# 1-Schematic_Task.net
KiCad netlist of a schematic drawn in EasyEDA
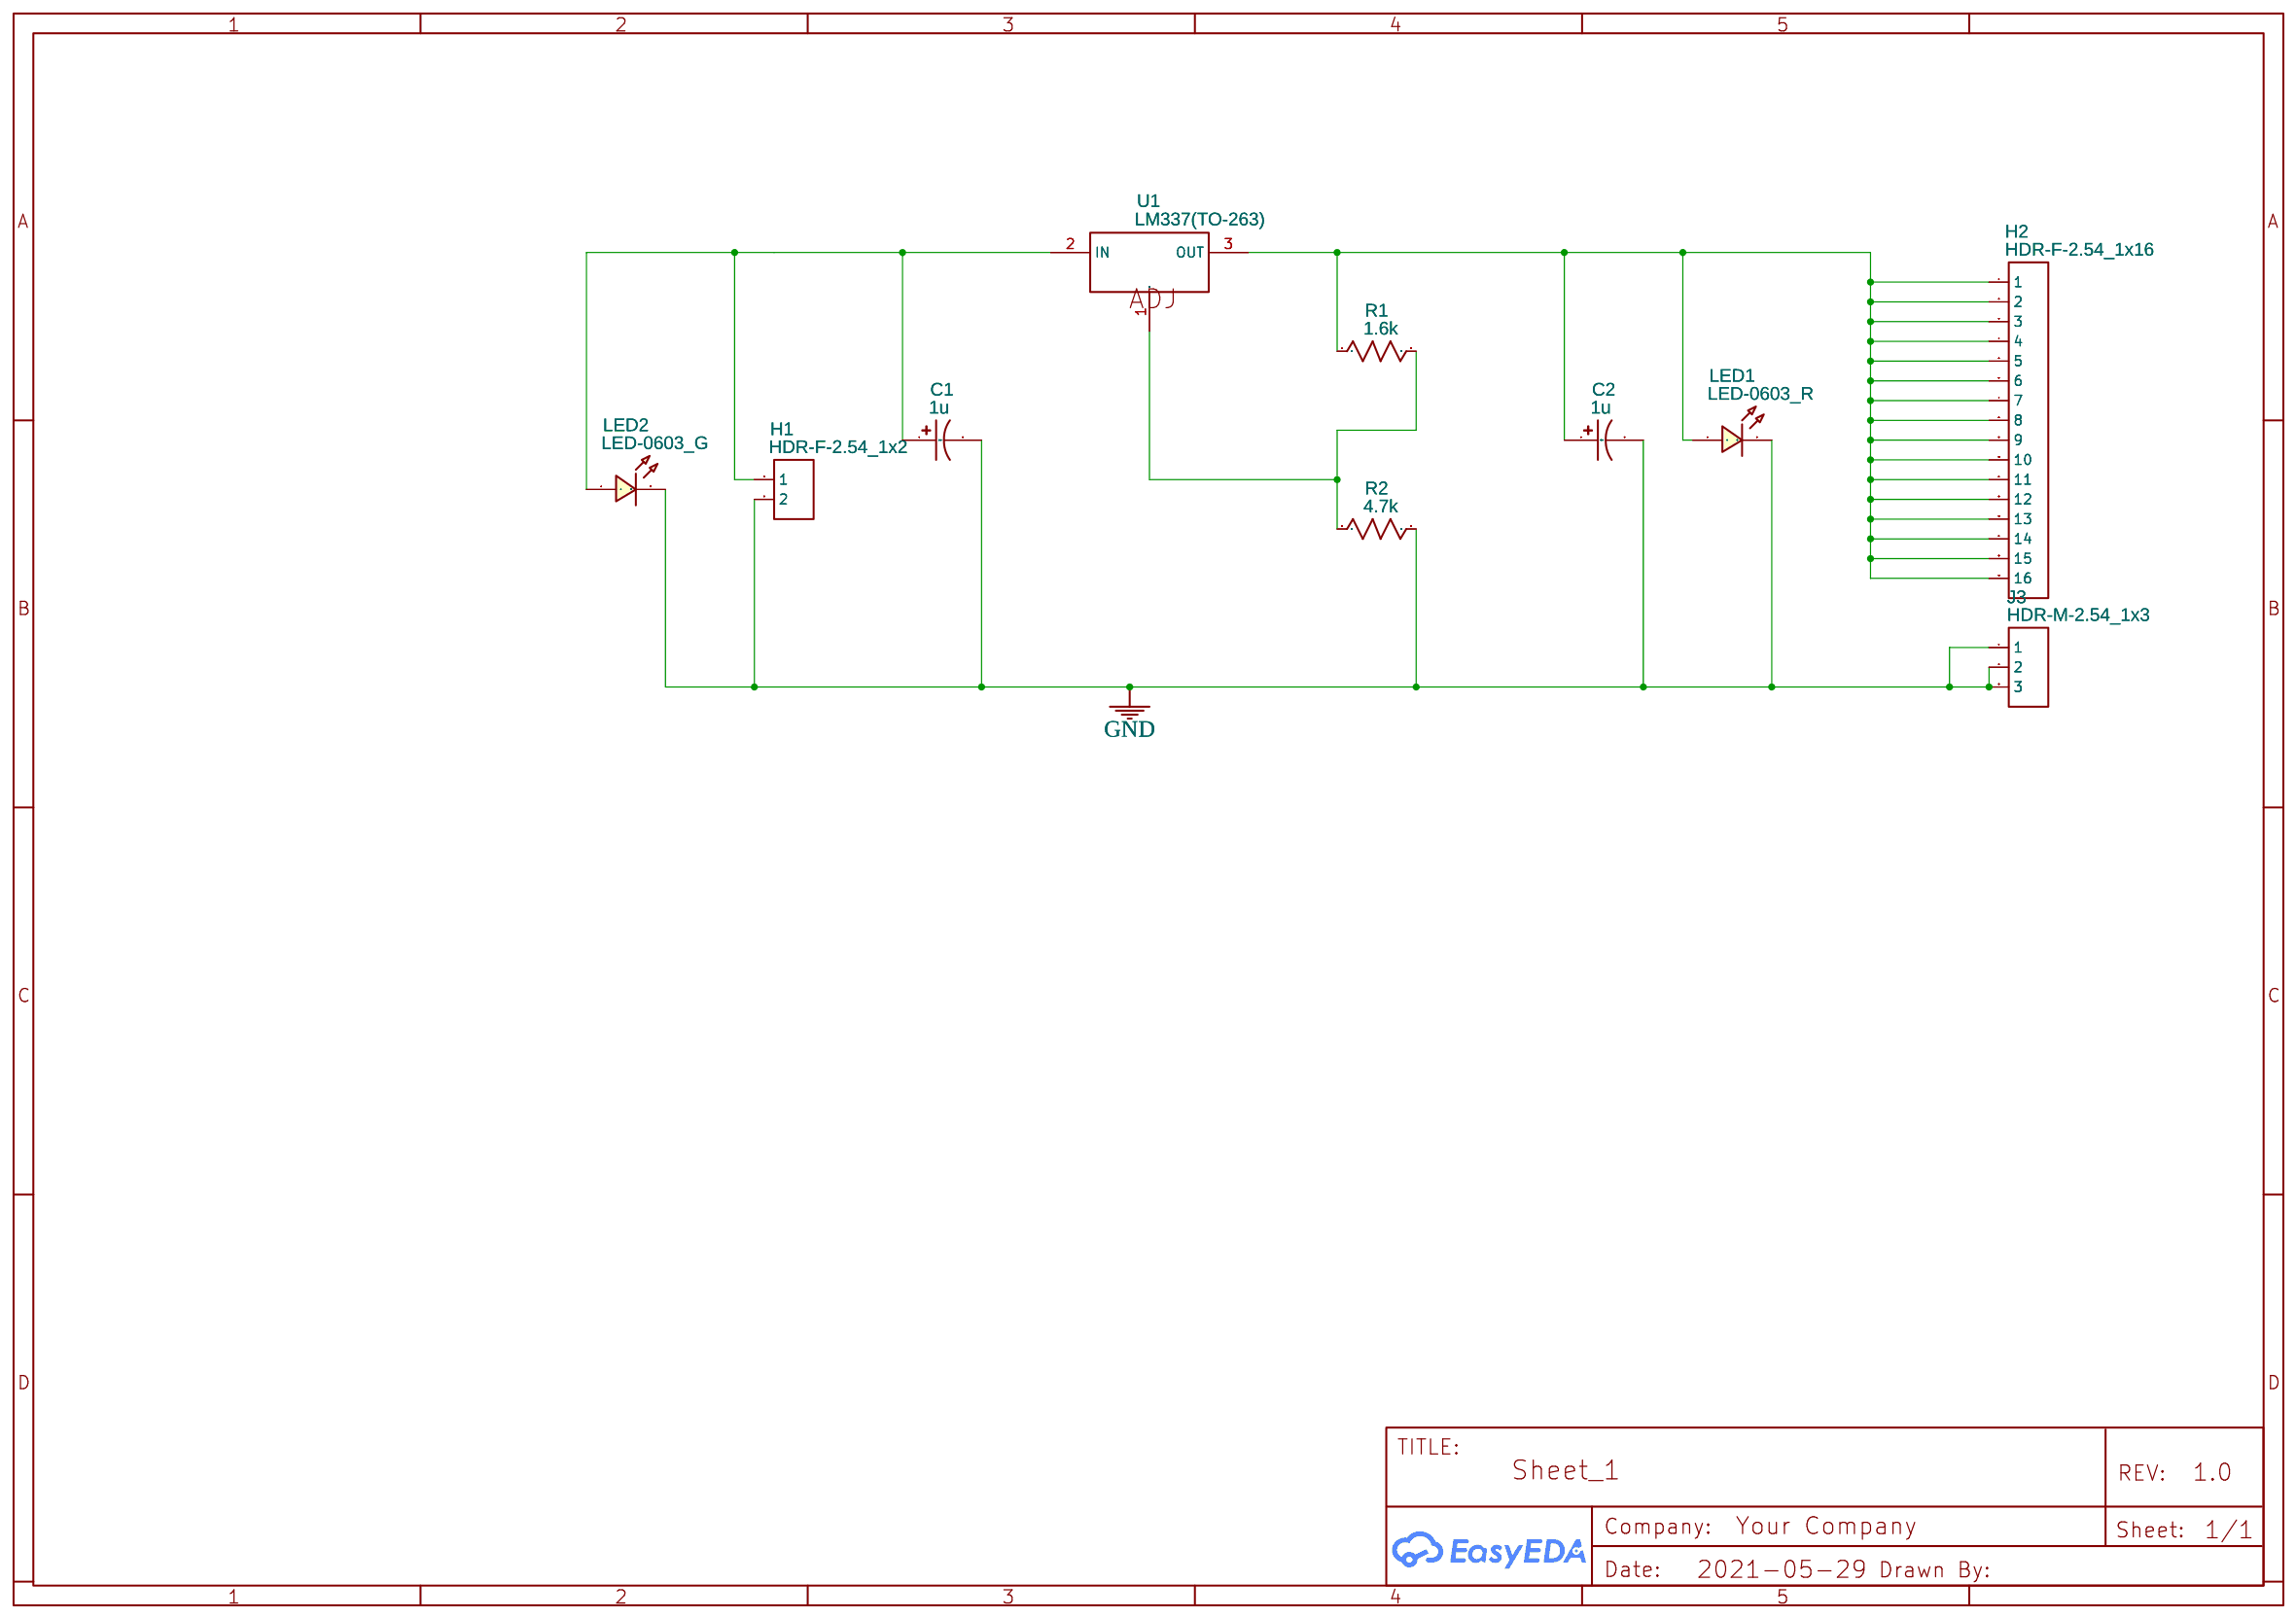
[diagram p0: schematic sheet]

(export (version "E")
  (design (tool "Eeschema 10.0.6"))
  (components
    (comp (ref "C1") (value "1u") (libsource (lib "") (part "C_Tan_SMD_A_US")))
    (comp (ref "C2") (value "1u") (libsource (lib "") (part "C_Tan_SMD_A_US")))
    (comp (ref "H1")
      (value "HDR-F-2.54_1x2")
      (fields (field (name "BOM_Supplier Part") "C49661"))
      (libsource (lib "") (part "HDR-F-2.54_1x2"))
    )
    (comp (ref "H2")
      (value "HDR-F-2.54_1x16")
      (fields (field (name "BOM_Supplier Part") "C66987"))
      (libsource (lib "") (part "HDR-F-2.54_1x16"))
    )
    (comp (ref "J3")
      (value "HDR-M-2.54_1x3")
      (fields (field (name "BOM_Supplier Part") "C180248"))
      (libsource (lib "") (part "HDR-M-2.54_1x3"))
    )
    (comp (ref "LED1")
      (value "LED-0603_R")
      (fields
        (field (name "BOM_Manufacturer Part") "19-217/R6C-AL1M2VY/3T")
        (field (name "BOM_Supplier Part") "C72044")
      )
      (libsource (lib "") (part "LED-0603_R"))
    )
    (comp (ref "LED2")
      (value "LED-0603_G")
      (fields
        (field (name "BOM_Manufacturer Part") "19-217/GHC-YR1S2/3T")
        (field (name "BOM_Supplier Part") "C72043")
      )
      (libsource (lib "") (part "LED-0603_G"))
    )
    (comp (ref "R1") (value "1.6k") (libsource (lib "") (part "R_0603_US")))
    (comp (ref "R2") (value "4.7k") (libsource (lib "") (part "R_0603_US")))
    (comp (ref "U1")
      (value "LM337(TO-263)")
      (fields (field (name "BOM_Manufacturer Part") "LM337D2TG") (field (name "BOM_Supplier Part") "C146782"))
      (libsource (lib "") (part "LM337(TO-263)"))
    )
  )
  (nets
    (net (code "1") (name "GND") (class "Default")
      (node (ref "C1") (pin "2") (pinfunction "2_2") (pintype "unspecified"))
      (node (ref "C2") (pin "2") (pinfunction "2_2") (pintype "unspecified"))
      (node (ref "H1") (pin "2") (pinfunction "2_2") (pintype "input"))
      (node (ref "J3") (pin "1") (pinfunction "1_1") (pintype "input"))
      (node (ref "J3") (pin "2") (pinfunction "2_2") (pintype "input"))
      (node (ref "J3") (pin "3") (pinfunction "3_3") (pintype "input"))
      (node (ref "LED1") (pin "2") (pinfunction "2_2") (pintype "unspecified"))
      (node (ref "LED2") (pin "2") (pinfunction "2_2") (pintype "unspecified"))
      (node (ref "R2") (pin "2") (pinfunction "2_2") (pintype "unspecified"))
    )
    (net (code "2") (name "Net-(U1-ADJ)") (class "Default")
      (node (ref "R1") (pin "2") (pinfunction "2_2") (pintype "unspecified"))
      (node (ref "R2") (pin "1") (pinfunction "1_1") (pintype "unspecified"))
      (node (ref "U1") (pin "1") (pinfunction "ADJ_1") (pintype "passive"))
    )
    (net (code "3") (name "Net-(U1-IN)") (class "Default")
      (node (ref "C1") (pin "1") (pinfunction "1_1") (pintype "unspecified"))
      (node (ref "H1") (pin "1") (pinfunction "1_1") (pintype "input"))
      (node (ref "LED2") (pin "1") (pinfunction "1_1") (pintype "unspecified"))
      (node (ref "U1") (pin "2") (pinfunction "IN_2") (pintype "passive"))
    )
    (net (code "4") (name "Net-(U1-OUT)") (class "Default")
      (node (ref "C2") (pin "1") (pinfunction "1_1") (pintype "unspecified"))
      (node (ref "H2") (pin "1") (pinfunction "1_1") (pintype "unspecified"))
      (node (ref "H2") (pin "10") (pinfunction "10_10") (pintype "unspecified"))
      (node (ref "H2") (pin "11") (pinfunction "11_11") (pintype "unspecified"))
      (node (ref "H2") (pin "12") (pinfunction "12_12") (pintype "unspecified"))
      (node (ref "H2") (pin "13") (pinfunction "13_13") (pintype "unspecified"))
      (node (ref "H2") (pin "14") (pinfunction "14_14") (pintype "unspecified"))
      (node (ref "H2") (pin "15") (pinfunction "15_15") (pintype "unspecified"))
      (node (ref "H2") (pin "16") (pinfunction "16_16") (pintype "unspecified"))
      (node (ref "H2") (pin "2") (pinfunction "2_2") (pintype "unspecified"))
      (node (ref "H2") (pin "3") (pinfunction "3_3") (pintype "unspecified"))
      (node (ref "H2") (pin "4") (pinfunction "4_4") (pintype "unspecified"))
      (node (ref "H2") (pin "5") (pinfunction "5_5") (pintype "unspecified"))
      (node (ref "H2") (pin "6") (pinfunction "6_6") (pintype "unspecified"))
      (node (ref "H2") (pin "7") (pinfunction "7_7") (pintype "unspecified"))
      (node (ref "H2") (pin "8") (pinfunction "8_8") (pintype "unspecified"))
      (node (ref "H2") (pin "9") (pinfunction "9_9") (pintype "unspecified"))
      (node (ref "LED1") (pin "1") (pinfunction "1_1") (pintype "unspecified"))
      (node (ref "R1") (pin "1") (pinfunction "1_1") (pintype "unspecified"))
      (node (ref "U1") (pin "3") (pinfunction "OUT_3") (pintype "passive"))
    )
  )
)
